# DDR4_Slot.net
KiCad netlist of a schematic drawn in Altium Designer
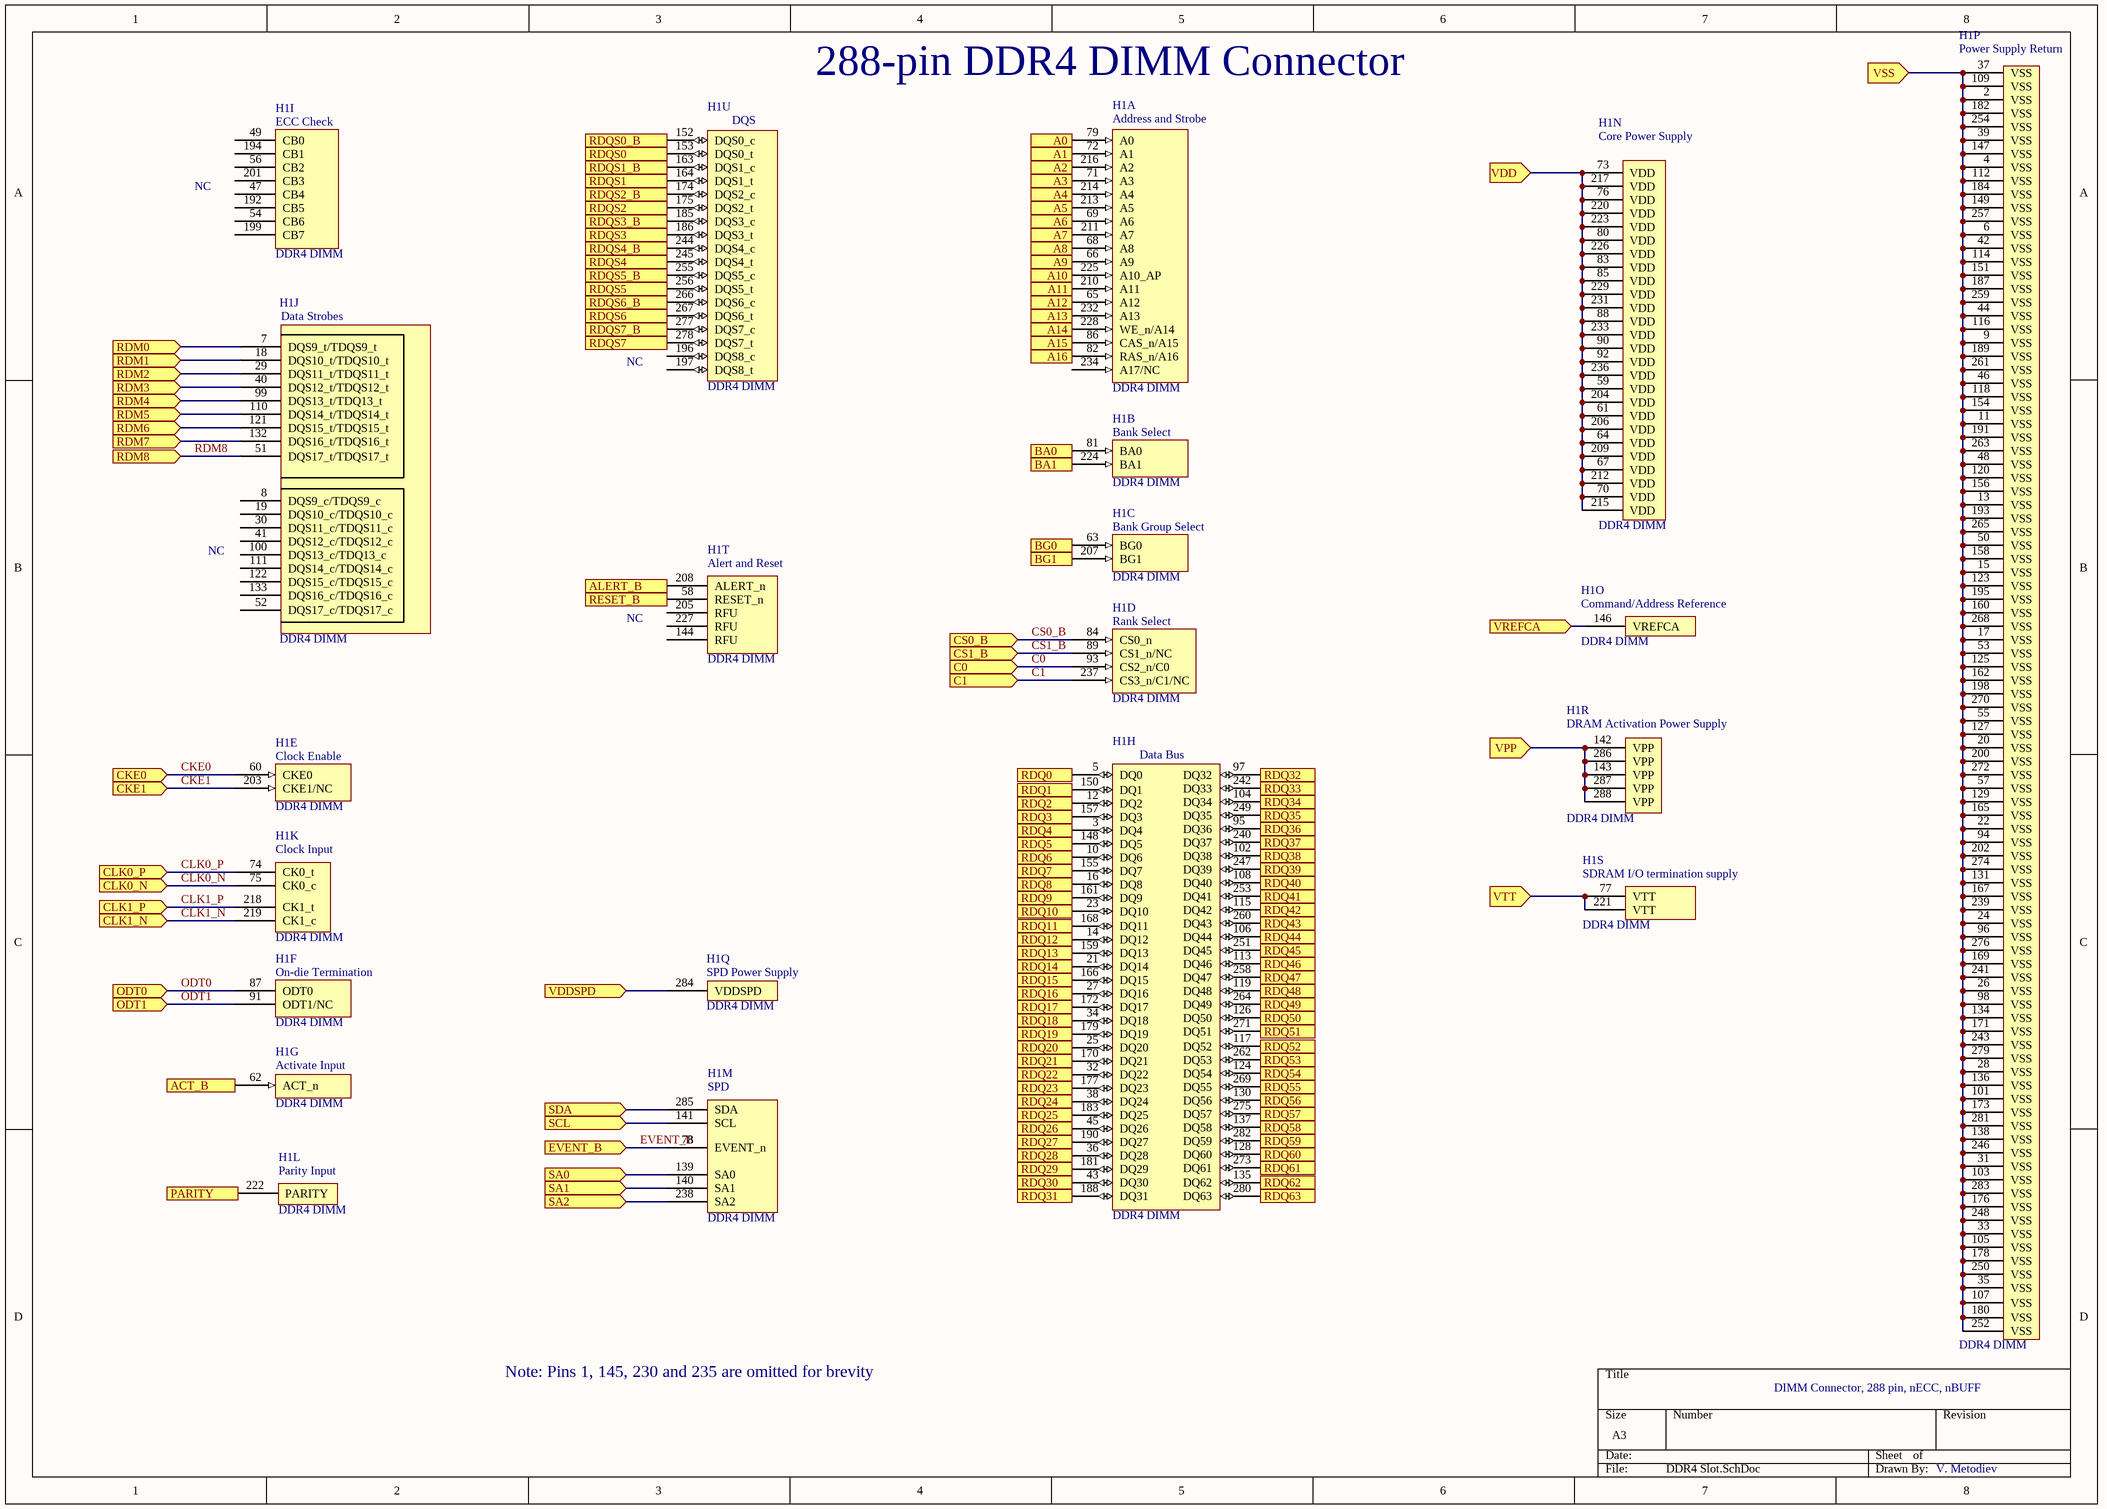
[diagram p0: DDR4 Slot.SchDoc]

(export (version "E")
  (design (tool "Eeschema 10.0.6"))
  (components
    (comp (ref "H1")
      (value "DDR4 DIMM")
      (footprint "DDR4 DIMM")
      (libsource (lib "RouterSchLib") (part "DDR4 DIMM"))
    )
  )
  (nets
    (net (code "1") (name "/A0") (class "Default")
      (node (ref "H1") (pin "79") (pinfunction "A0_79") (pintype "input"))
    )
    (net (code "2") (name "/A1") (class "Default")
      (node (ref "H1") (pin "72") (pinfunction "A1_72") (pintype "input"))
    )
    (net (code "3") (name "/A2") (class "Default")
      (node (ref "H1") (pin "216") (pinfunction "A2_216") (pintype "input"))
    )
    (net (code "4") (name "/A3") (class "Default")
      (node (ref "H1") (pin "71") (pinfunction "A3_71") (pintype "input"))
    )
    (net (code "5") (name "/A4") (class "Default")
      (node (ref "H1") (pin "214") (pinfunction "A4_214") (pintype "input"))
    )
    (net (code "6") (name "/A5") (class "Default")
      (node (ref "H1") (pin "213") (pinfunction "A5_213") (pintype "input"))
    )
    (net (code "7") (name "/A6") (class "Default")
      (node (ref "H1") (pin "69") (pinfunction "A6_69") (pintype "input"))
    )
    (net (code "8") (name "/A7") (class "Default")
      (node (ref "H1") (pin "211") (pinfunction "A7_211") (pintype "input"))
    )
    (net (code "9") (name "/A8") (class "Default")
      (node (ref "H1") (pin "68") (pinfunction "A8_68") (pintype "input"))
    )
    (net (code "10") (name "/A9") (class "Default")
      (node (ref "H1") (pin "66") (pinfunction "A9_66") (pintype "input"))
    )
    (net (code "11") (name "/A10") (class "Default")
      (node (ref "H1") (pin "225") (pinfunction "A10_AP_225") (pintype "input"))
    )
    (net (code "12") (name "/A11") (class "Default")
      (node (ref "H1") (pin "210") (pinfunction "A11_210") (pintype "input"))
    )
    (net (code "13") (name "/A12") (class "Default")
      (node (ref "H1") (pin "65") (pinfunction "A12_65") (pintype "input"))
    )
    (net (code "14") (name "/A13") (class "Default")
      (node (ref "H1") (pin "232") (pinfunction "A13_232") (pintype "input"))
    )
    (net (code "15") (name "/A14") (class "Default")
      (node (ref "H1") (pin "228") (pinfunction "WE_n/A14_228") (pintype "input"))
    )
    (net (code "16") (name "/A15") (class "Default")
      (node (ref "H1") (pin "86") (pinfunction "CAS_n/A15_86") (pintype "input"))
    )
    (net (code "17") (name "/A16") (class "Default")
      (node (ref "H1") (pin "82") (pinfunction "RAS_n/A16_82") (pintype "input"))
    )
    (net (code "18") (name "/ACT_B") (class "Default")
      (node (ref "H1") (pin "62") (pinfunction "ACT_n_62") (pintype "input"))
    )
    (net (code "19") (name "/ALERT_B") (class "Default")
      (node (ref "H1") (pin "208") (pinfunction "ALERT_n_208") (pintype "passive"))
    )
    (net (code "20") (name "/BA0") (class "Default")
      (node (ref "H1") (pin "81") (pinfunction "BA0_81") (pintype "input"))
    )
    (net (code "21") (name "/BA1") (class "Default")
      (node (ref "H1") (pin "224") (pinfunction "BA1_224") (pintype "input"))
    )
    (net (code "22") (name "/BG0") (class "Default")
      (node (ref "H1") (pin "63") (pinfunction "BG0_63") (pintype "input"))
    )
    (net (code "23") (name "/BG1") (class "Default")
      (node (ref "H1") (pin "207") (pinfunction "BG1_207") (pintype "input"))
    )
    (net (code "24") (name "/C0") (class "Default")
      (node (ref "H1") (pin "93") (pinfunction "CS2_n/C0_93") (pintype "input"))
    )
    (net (code "25") (name "/C1") (class "Default")
      (node (ref "H1") (pin "237") (pinfunction "CS3_n/C1/NC_237") (pintype "input"))
    )
    (net (code "26") (name "/CKE0") (class "Default")
      (node (ref "H1") (pin "60") (pinfunction "CKE0_60") (pintype "input"))
    )
    (net (code "27") (name "/CKE1") (class "Default")
      (node (ref "H1") (pin "203") (pinfunction "CKE1/NC_203") (pintype "input"))
    )
    (net (code "28") (name "/CLK0_N") (class "Default")
      (node (ref "H1") (pin "75") (pinfunction "CK0_c_75") (pintype "passive"))
    )
    (net (code "29") (name "/CLK0_P") (class "Default")
      (node (ref "H1") (pin "74") (pinfunction "CK0_t_74") (pintype "passive"))
    )
    (net (code "30") (name "/CLK1_N") (class "Default")
      (node (ref "H1") (pin "219") (pinfunction "CK1_c_219") (pintype "passive"))
    )
    (net (code "31") (name "/CLK1_P") (class "Default")
      (node (ref "H1") (pin "218") (pinfunction "CK1_t_218") (pintype "passive"))
    )
    (net (code "32") (name "/CS0_B") (class "Default")
      (node (ref "H1") (pin "84") (pinfunction "CS0_n_84") (pintype "input"))
    )
    (net (code "33") (name "/CS1_B") (class "Default")
      (node (ref "H1") (pin "89") (pinfunction "CS1_n/NC_89") (pintype "input"))
    )
    (net (code "34") (name "/EVENT_B") (class "Default")
      (node (ref "H1") (pin "78") (pinfunction "EVENT_n_78") (pintype "passive"))
    )
    (net (code "35") (name "/ODT0") (class "Default")
      (node (ref "H1") (pin "87") (pinfunction "ODT0_87") (pintype "passive"))
    )
    (net (code "36") (name "/ODT1") (class "Default")
      (node (ref "H1") (pin "91") (pinfunction "ODT1/NC_91") (pintype "passive"))
    )
    (net (code "37") (name "/PARITY") (class "Default")
      (node (ref "H1") (pin "222") (pinfunction "PARITY_222") (pintype "passive"))
    )
    (net (code "38") (name "/RDM0") (class "Default")
      (node (ref "H1") (pin "7") (pinfunction "DQS9_t/TDQS9_t_7") (pintype "passive"))
    )
    (net (code "39") (name "/RDM1") (class "Default")
      (node (ref "H1") (pin "18") (pinfunction "DQS10_t/TDQS10_t_18") (pintype "passive"))
    )
    (net (code "40") (name "/RDM2") (class "Default")
      (node (ref "H1") (pin "29") (pinfunction "DQS11_t/TDQS11_t_29") (pintype "passive"))
    )
    (net (code "41") (name "/RDM3") (class "Default")
      (node (ref "H1") (pin "40") (pinfunction "DQS12_t/TDQS12_t_40") (pintype "passive"))
    )
    (net (code "42") (name "/RDM4") (class "Default")
      (node (ref "H1") (pin "99") (pinfunction "DQS13_t/TDQ13_t_99") (pintype "passive"))
    )
    (net (code "43") (name "/RDM5") (class "Default")
      (node (ref "H1") (pin "110") (pinfunction "DQS14_t/TDQS14_t_110") (pintype "passive"))
    )
    (net (code "44") (name "/RDM6") (class "Default")
      (node (ref "H1") (pin "121") (pinfunction "DQS15_t/TDQS15_t_121") (pintype "passive"))
    )
    (net (code "45") (name "/RDM7") (class "Default")
      (node (ref "H1") (pin "132") (pinfunction "DQS16_t/TDQS16_t_132") (pintype "passive"))
    )
    (net (code "46") (name "/RDM8") (class "Default")
      (node (ref "H1") (pin "51") (pinfunction "DQS17_t/TDQS17_t_51") (pintype "passive"))
    )
    (net (code "47") (name "/RDQ0") (class "Default")
      (node (ref "H1") (pin "5") (pinfunction "DQ0_5") (pintype "bidirectional"))
    )
    (net (code "48") (name "/RDQ1") (class "Default")
      (node (ref "H1") (pin "150") (pinfunction "DQ1_150") (pintype "bidirectional"))
    )
    (net (code "49") (name "/RDQ2") (class "Default")
      (node (ref "H1") (pin "12") (pinfunction "DQ2_12") (pintype "bidirectional"))
    )
    (net (code "50") (name "/RDQ3") (class "Default")
      (node (ref "H1") (pin "157") (pinfunction "DQ3_157") (pintype "bidirectional"))
    )
    (net (code "51") (name "/RDQ4") (class "Default")
      (node (ref "H1") (pin "3") (pinfunction "DQ4_3") (pintype "bidirectional"))
    )
    (net (code "52") (name "/RDQ5") (class "Default")
      (node (ref "H1") (pin "148") (pinfunction "DQ5_148") (pintype "bidirectional"))
    )
    (net (code "53") (name "/RDQ6") (class "Default")
      (node (ref "H1") (pin "10") (pinfunction "DQ6_10") (pintype "bidirectional"))
    )
    (net (code "54") (name "/RDQ7") (class "Default")
      (node (ref "H1") (pin "155") (pinfunction "DQ7_155") (pintype "bidirectional"))
    )
    (net (code "55") (name "/RDQ8") (class "Default")
      (node (ref "H1") (pin "16") (pinfunction "DQ8_16") (pintype "bidirectional"))
    )
    (net (code "56") (name "/RDQ9") (class "Default")
      (node (ref "H1") (pin "161") (pinfunction "DQ9_161") (pintype "bidirectional"))
    )
    (net (code "57") (name "/RDQ10") (class "Default")
      (node (ref "H1") (pin "23") (pinfunction "DQ10_23") (pintype "bidirectional"))
    )
    (net (code "58") (name "/RDQ11") (class "Default")
      (node (ref "H1") (pin "168") (pinfunction "DQ11_168") (pintype "bidirectional"))
    )
    (net (code "59") (name "/RDQ12") (class "Default")
      (node (ref "H1") (pin "14") (pinfunction "DQ12_14") (pintype "bidirectional"))
    )
    (net (code "60") (name "/RDQ13") (class "Default")
      (node (ref "H1") (pin "159") (pinfunction "DQ13_159") (pintype "bidirectional"))
    )
    (net (code "61") (name "/RDQ14") (class "Default")
      (node (ref "H1") (pin "21") (pinfunction "DQ14_21") (pintype "bidirectional"))
    )
    (net (code "62") (name "/RDQ15") (class "Default")
      (node (ref "H1") (pin "166") (pinfunction "DQ15_166") (pintype "bidirectional"))
    )
    (net (code "63") (name "/RDQ16") (class "Default")
      (node (ref "H1") (pin "27") (pinfunction "DQ16_27") (pintype "bidirectional"))
    )
    (net (code "64") (name "/RDQ17") (class "Default")
      (node (ref "H1") (pin "172") (pinfunction "DQ17_172") (pintype "bidirectional"))
    )
    (net (code "65") (name "/RDQ18") (class "Default")
      (node (ref "H1") (pin "34") (pinfunction "DQ18_34") (pintype "bidirectional"))
    )
    (net (code "66") (name "/RDQ19") (class "Default")
      (node (ref "H1") (pin "179") (pinfunction "DQ19_179") (pintype "bidirectional"))
    )
    (net (code "67") (name "/RDQ20") (class "Default")
      (node (ref "H1") (pin "25") (pinfunction "DQ20_25") (pintype "bidirectional"))
    )
    (net (code "68") (name "/RDQ21") (class "Default")
      (node (ref "H1") (pin "170") (pinfunction "DQ21_170") (pintype "bidirectional"))
    )
    (net (code "69") (name "/RDQ22") (class "Default")
      (node (ref "H1") (pin "32") (pinfunction "DQ22_32") (pintype "bidirectional"))
    )
    (net (code "70") (name "/RDQ23") (class "Default")
      (node (ref "H1") (pin "177") (pinfunction "DQ23_177") (pintype "bidirectional"))
    )
    (net (code "71") (name "/RDQ24") (class "Default")
      (node (ref "H1") (pin "38") (pinfunction "DQ24_38") (pintype "bidirectional"))
    )
    (net (code "72") (name "/RDQ25") (class "Default")
      (node (ref "H1") (pin "183") (pinfunction "DQ25_183") (pintype "bidirectional"))
    )
    (net (code "73") (name "/RDQ26") (class "Default")
      (node (ref "H1") (pin "45") (pinfunction "DQ26_45") (pintype "bidirectional"))
    )
    (net (code "74") (name "/RDQ27") (class "Default")
      (node (ref "H1") (pin "190") (pinfunction "DQ27_190") (pintype "bidirectional"))
    )
    (net (code "75") (name "/RDQ28") (class "Default")
      (node (ref "H1") (pin "36") (pinfunction "DQ28_36") (pintype "bidirectional"))
    )
    (net (code "76") (name "/RDQ29") (class "Default")
      (node (ref "H1") (pin "181") (pinfunction "DQ29_181") (pintype "bidirectional"))
    )
    (net (code "77") (name "/RDQ30") (class "Default")
      (node (ref "H1") (pin "43") (pinfunction "DQ30_43") (pintype "bidirectional"))
    )
    (net (code "78") (name "/RDQ31") (class "Default")
      (node (ref "H1") (pin "188") (pinfunction "DQ31_188") (pintype "bidirectional"))
    )
    (net (code "79") (name "/RDQ32") (class "Default")
      (node (ref "H1") (pin "97") (pinfunction "DQ32_97") (pintype "bidirectional"))
    )
    (net (code "80") (name "/RDQ33") (class "Default")
      (node (ref "H1") (pin "242") (pinfunction "DQ33_242") (pintype "bidirectional"))
    )
    (net (code "81") (name "/RDQ34") (class "Default")
      (node (ref "H1") (pin "104") (pinfunction "DQ34_104") (pintype "bidirectional"))
    )
    (net (code "82") (name "/RDQ35") (class "Default")
      (node (ref "H1") (pin "249") (pinfunction "DQ35_249") (pintype "bidirectional"))
    )
    (net (code "83") (name "/RDQ36") (class "Default")
      (node (ref "H1") (pin "95") (pinfunction "DQ36_95") (pintype "bidirectional"))
    )
    (net (code "84") (name "/RDQ37") (class "Default")
      (node (ref "H1") (pin "240") (pinfunction "DQ37_240") (pintype "bidirectional"))
    )
    (net (code "85") (name "/RDQ38") (class "Default")
      (node (ref "H1") (pin "102") (pinfunction "DQ38_102") (pintype "bidirectional"))
    )
    (net (code "86") (name "/RDQ39") (class "Default")
      (node (ref "H1") (pin "247") (pinfunction "DQ39_247") (pintype "bidirectional"))
    )
    (net (code "87") (name "/RDQ40") (class "Default")
      (node (ref "H1") (pin "108") (pinfunction "DQ40_108") (pintype "bidirectional"))
    )
    (net (code "88") (name "/RDQ41") (class "Default")
      (node (ref "H1") (pin "253") (pinfunction "DQ41_253") (pintype "bidirectional"))
    )
    (net (code "89") (name "/RDQ42") (class "Default")
      (node (ref "H1") (pin "115") (pinfunction "DQ42_115") (pintype "bidirectional"))
    )
    (net (code "90") (name "/RDQ43") (class "Default")
      (node (ref "H1") (pin "260") (pinfunction "DQ43_260") (pintype "bidirectional"))
    )
    (net (code "91") (name "/RDQ44") (class "Default")
      (node (ref "H1") (pin "106") (pinfunction "DQ44_106") (pintype "bidirectional"))
    )
    (net (code "92") (name "/RDQ45") (class "Default")
      (node (ref "H1") (pin "251") (pinfunction "DQ45_251") (pintype "bidirectional"))
    )
    (net (code "93") (name "/RDQ46") (class "Default")
      (node (ref "H1") (pin "113") (pinfunction "DQ46_113") (pintype "bidirectional"))
    )
    (net (code "94") (name "/RDQ47") (class "Default")
      (node (ref "H1") (pin "258") (pinfunction "DQ47_258") (pintype "bidirectional"))
    )
    (net (code "95") (name "/RDQ48") (class "Default")
      (node (ref "H1") (pin "119") (pinfunction "DQ48_119") (pintype "bidirectional"))
    )
    (net (code "96") (name "/RDQ49") (class "Default")
      (node (ref "H1") (pin "264") (pinfunction "DQ49_264") (pintype "bidirectional"))
    )
    (net (code "97") (name "/RDQ50") (class "Default")
      (node (ref "H1") (pin "126") (pinfunction "DQ50_126") (pintype "bidirectional"))
    )
    (net (code "98") (name "/RDQ51") (class "Default")
      (node (ref "H1") (pin "271") (pinfunction "DQ51_271") (pintype "bidirectional"))
    )
    (net (code "99") (name "/RDQ52") (class "Default")
      (node (ref "H1") (pin "117") (pinfunction "DQ52_117") (pintype "bidirectional"))
    )
    (net (code "100") (name "/RDQ53") (class "Default")
      (node (ref "H1") (pin "262") (pinfunction "DQ53_262") (pintype "bidirectional"))
    )
    (net (code "101") (name "/RDQ54") (class "Default")
      (node (ref "H1") (pin "124") (pinfunction "DQ54_124") (pintype "bidirectional"))
    )
    (net (code "102") (name "/RDQ55") (class "Default")
      (node (ref "H1") (pin "269") (pinfunction "DQ55_269") (pintype "bidirectional"))
    )
    (net (code "103") (name "/RDQ56") (class "Default")
      (node (ref "H1") (pin "130") (pinfunction "DQ56_130") (pintype "bidirectional"))
    )
    (net (code "104") (name "/RDQ57") (class "Default")
      (node (ref "H1") (pin "275") (pinfunction "DQ57_275") (pintype "bidirectional"))
    )
    (net (code "105") (name "/RDQ58") (class "Default")
      (node (ref "H1") (pin "137") (pinfunction "DQ58_137") (pintype "bidirectional"))
    )
    (net (code "106") (name "/RDQ59") (class "Default")
      (node (ref "H1") (pin "282") (pinfunction "DQ59_282") (pintype "bidirectional"))
    )
    (net (code "107") (name "/RDQ60") (class "Default")
      (node (ref "H1") (pin "128") (pinfunction "DQ60_128") (pintype "bidirectional"))
    )
    (net (code "108") (name "/RDQ61") (class "Default")
      (node (ref "H1") (pin "273") (pinfunction "DQ61_273") (pintype "bidirectional"))
    )
    (net (code "109") (name "/RDQ62") (class "Default")
      (node (ref "H1") (pin "135") (pinfunction "DQ62_135") (pintype "bidirectional"))
    )
    (net (code "110") (name "/RDQ63") (class "Default")
      (node (ref "H1") (pin "280") (pinfunction "DQ63_280") (pintype "bidirectional"))
    )
    (net (code "111") (name "/RDQS0") (class "Default")
      (node (ref "H1") (pin "153") (pinfunction "DQS0_t_153") (pintype "bidirectional"))
    )
    (net (code "112") (name "/RDQS0_B") (class "Default")
      (node (ref "H1") (pin "152") (pinfunction "DQS0_c_152") (pintype "bidirectional"))
    )
    (net (code "113") (name "/RDQS1") (class "Default")
      (node (ref "H1") (pin "164") (pinfunction "DQS1_t_164") (pintype "bidirectional"))
    )
    (net (code "114") (name "/RDQS1_B") (class "Default")
      (node (ref "H1") (pin "163") (pinfunction "DQS1_c_163") (pintype "bidirectional"))
    )
    (net (code "115") (name "/RDQS2") (class "Default")
      (node (ref "H1") (pin "175") (pinfunction "DQS2_t_175") (pintype "bidirectional"))
    )
    (net (code "116") (name "/RDQS2_B") (class "Default")
      (node (ref "H1") (pin "174") (pinfunction "DQS2_c_174") (pintype "bidirectional"))
    )
    (net (code "117") (name "/RDQS3") (class "Default")
      (node (ref "H1") (pin "186") (pinfunction "DQS3_t_186") (pintype "bidirectional"))
    )
    (net (code "118") (name "/RDQS3_B") (class "Default")
      (node (ref "H1") (pin "185") (pinfunction "DQS3_c_185") (pintype "bidirectional"))
    )
    (net (code "119") (name "/RDQS4") (class "Default")
      (node (ref "H1") (pin "245") (pinfunction "DQS4_t_245") (pintype "bidirectional"))
    )
    (net (code "120") (name "/RDQS4_B") (class "Default")
      (node (ref "H1") (pin "244") (pinfunction "DQS4_c_244") (pintype "bidirectional"))
    )
    (net (code "121") (name "/RDQS5") (class "Default")
      (node (ref "H1") (pin "256") (pinfunction "DQS5_t_256") (pintype "bidirectional"))
    )
    (net (code "122") (name "/RDQS5_B") (class "Default")
      (node (ref "H1") (pin "255") (pinfunction "DQS5_c_255") (pintype "bidirectional"))
    )
    (net (code "123") (name "/RDQS6") (class "Default")
      (node (ref "H1") (pin "267") (pinfunction "DQS6_t_267") (pintype "bidirectional"))
    )
    (net (code "124") (name "/RDQS6_B") (class "Default")
      (node (ref "H1") (pin "266") (pinfunction "DQS6_c_266") (pintype "bidirectional"))
    )
    (net (code "125") (name "/RDQS7") (class "Default")
      (node (ref "H1") (pin "278") (pinfunction "DQS7_t_278") (pintype "bidirectional"))
    )
    (net (code "126") (name "/RDQS7_B") (class "Default")
      (node (ref "H1") (pin "277") (pinfunction "DQS7_c_277") (pintype "bidirectional"))
    )
    (net (code "127") (name "/RESET_B") (class "Default")
      (node (ref "H1") (pin "58") (pinfunction "RESET_n_58") (pintype "passive"))
    )
    (net (code "128") (name "/SA0") (class "Default")
      (node (ref "H1") (pin "139") (pinfunction "SA0_139") (pintype "passive"))
    )
    (net (code "129") (name "/SA1") (class "Default")
      (node (ref "H1") (pin "140") (pinfunction "SA1_140") (pintype "passive"))
    )
    (net (code "130") (name "/SA2") (class "Default")
      (node (ref "H1") (pin "238") (pinfunction "SA2_238") (pintype "passive"))
    )
    (net (code "131") (name "/SCL") (class "Default")
      (node (ref "H1") (pin "141") (pinfunction "SCL_141") (pintype "passive"))
    )
    (net (code "132") (name "/SDA") (class "Default")
      (node (ref "H1") (pin "285") (pinfunction "SDA_285") (pintype "passive"))
    )
    (net (code "133") (name "/VDD") (class "Default")
      (node (ref "H1") (pin "204") (pinfunction "VDD_204") (pintype "passive"))
      (node (ref "H1") (pin "206") (pinfunction "VDD_206") (pintype "passive"))
      (node (ref "H1") (pin "209") (pinfunction "VDD_209") (pintype "passive"))
      (node (ref "H1") (pin "212") (pinfunction "VDD_212") (pintype "passive"))
      (node (ref "H1") (pin "215") (pinfunction "VDD_215") (pintype "passive"))
      (node (ref "H1") (pin "217") (pinfunction "VDD_217") (pintype "passive"))
      (node (ref "H1") (pin "220") (pinfunction "VDD_220") (pintype "passive"))
      (node (ref "H1") (pin "223") (pinfunction "VDD_223") (pintype "passive"))
      (node (ref "H1") (pin "226") (pinfunction "VDD_226") (pintype "passive"))
      (node (ref "H1") (pin "229") (pinfunction "VDD_229") (pintype "passive"))
      (node (ref "H1") (pin "231") (pinfunction "VDD_231") (pintype "passive"))
      (node (ref "H1") (pin "233") (pinfunction "VDD_233") (pintype "passive"))
      (node (ref "H1") (pin "236") (pinfunction "VDD_236") (pintype "passive"))
      (node (ref "H1") (pin "59") (pinfunction "VDD_59") (pintype "passive"))
      (node (ref "H1") (pin "61") (pinfunction "VDD_61") (pintype "passive"))
      (node (ref "H1") (pin "64") (pinfunction "VDD_64") (pintype "passive"))
      (node (ref "H1") (pin "67") (pinfunction "VDD_67") (pintype "passive"))
      (node (ref "H1") (pin "70") (pinfunction "VDD_70") (pintype "passive"))
      (node (ref "H1") (pin "73") (pinfunction "VDD_73") (pintype "passive"))
      (node (ref "H1") (pin "76") (pinfunction "VDD_76") (pintype "passive"))
      (node (ref "H1") (pin "80") (pinfunction "VDD_80") (pintype "passive"))
      (node (ref "H1") (pin "83") (pinfunction "VDD_83") (pintype "passive"))
      (node (ref "H1") (pin "85") (pinfunction "VDD_85") (pintype "passive"))
      (node (ref "H1") (pin "88") (pinfunction "VDD_88") (pintype "passive"))
      (node (ref "H1") (pin "90") (pinfunction "VDD_90") (pintype "passive"))
      (node (ref "H1") (pin "92") (pinfunction "VDD_92") (pintype "passive"))
    )
    (net (code "134") (name "/VDDSPD") (class "Default")
      (node (ref "H1") (pin "284") (pinfunction "VDDSPD_284") (pintype "passive"))
    )
    (net (code "135") (name "/VPP") (class "Default")
      (node (ref "H1") (pin "142") (pinfunction "VPP_142") (pintype "passive"))
      (node (ref "H1") (pin "143") (pinfunction "VPP_143") (pintype "passive"))
      (node (ref "H1") (pin "286") (pinfunction "VPP_286") (pintype "passive"))
      (node (ref "H1") (pin "287") (pinfunction "VPP_287") (pintype "passive"))
      (node (ref "H1") (pin "288") (pinfunction "VPP_288") (pintype "passive"))
    )
    (net (code "136") (name "/VREFCA") (class "Default")
      (node (ref "H1") (pin "146") (pinfunction "VREFCA_146") (pintype "passive"))
    )
    (net (code "137") (name "/VSS") (class "Default")
      (node (ref "H1") (pin "101") (pinfunction "VSS_101") (pintype "passive"))
      (node (ref "H1") (pin "103") (pinfunction "VSS_103") (pintype "passive"))
      (node (ref "H1") (pin "105") (pinfunction "VSS_105") (pintype "passive"))
      (node (ref "H1") (pin "107") (pinfunction "VSS_107") (pintype "passive"))
      (node (ref "H1") (pin "109") (pinfunction "VSS_109") (pintype "passive"))
      (node (ref "H1") (pin "11") (pinfunction "VSS_11") (pintype "passive"))
      (node (ref "H1") (pin "112") (pinfunction "VSS_112") (pintype "passive"))
      (node (ref "H1") (pin "114") (pinfunction "VSS_114") (pintype "passive"))
      (node (ref "H1") (pin "116") (pinfunction "VSS_116") (pintype "passive"))
      (node (ref "H1") (pin "118") (pinfunction "VSS_118") (pintype "passive"))
      (node (ref "H1") (pin "120") (pinfunction "VSS_120") (pintype "passive"))
      (node (ref "H1") (pin "123") (pinfunction "VSS_123") (pintype "passive"))
      (node (ref "H1") (pin "125") (pinfunction "VSS_125") (pintype "passive"))
      (node (ref "H1") (pin "127") (pinfunction "VSS_127") (pintype "passive"))
      (node (ref "H1") (pin "129") (pinfunction "VSS_129") (pintype "passive"))
      (node (ref "H1") (pin "13") (pinfunction "VSS_13") (pintype "passive"))
      (node (ref "H1") (pin "131") (pinfunction "VSS_131") (pintype "passive"))
      (node (ref "H1") (pin "134") (pinfunction "VSS_134") (pintype "passive"))
      (node (ref "H1") (pin "136") (pinfunction "VSS_136") (pintype "passive"))
      (node (ref "H1") (pin "138") (pinfunction "VSS_138") (pintype "passive"))
      (node (ref "H1") (pin "147") (pinfunction "VSS_147") (pintype "passive"))
      (node (ref "H1") (pin "149") (pinfunction "VSS_149") (pintype "passive"))
      (node (ref "H1") (pin "15") (pinfunction "VSS_15") (pintype "passive"))
      (node (ref "H1") (pin "151") (pinfunction "VSS_151") (pintype "passive"))
      (node (ref "H1") (pin "154") (pinfunction "VSS_154") (pintype "passive"))
      (node (ref "H1") (pin "156") (pinfunction "VSS_156") (pintype "passive"))
      (node (ref "H1") (pin "158") (pinfunction "VSS_158") (pintype "passive"))
      (node (ref "H1") (pin "160") (pinfunction "VSS_160") (pintype "passive"))
      (node (ref "H1") (pin "162") (pinfunction "VSS_162") (pintype "passive"))
      (node (ref "H1") (pin "165") (pinfunction "VSS_165") (pintype "passive"))
      (node (ref "H1") (pin "167") (pinfunction "VSS_167") (pintype "passive"))
      (node (ref "H1") (pin "169") (pinfunction "VSS_169") (pintype "passive"))
      (node (ref "H1") (pin "17") (pinfunction "VSS_17") (pintype "passive"))
      (node (ref "H1") (pin "171") (pinfunction "VSS_171") (pintype "passive"))
      (node (ref "H1") (pin "173") (pinfunction "VSS_173") (pintype "passive"))
      (node (ref "H1") (pin "176") (pinfunction "VSS_176") (pintype "passive"))
      (node (ref "H1") (pin "178") (pinfunction "VSS_178") (pintype "passive"))
      (node (ref "H1") (pin "180") (pinfunction "VSS_180") (pintype "passive"))
      (node (ref "H1") (pin "182") (pinfunction "VSS_182") (pintype "passive"))
      (node (ref "H1") (pin "184") (pinfunction "VSS_184") (pintype "passive"))
      (node (ref "H1") (pin "187") (pinfunction "VSS_187") (pintype "passive"))
      (node (ref "H1") (pin "189") (pinfunction "VSS_189") (pintype "passive"))
      (node (ref "H1") (pin "191") (pinfunction "VSS_191") (pintype "passive"))
      (node (ref "H1") (pin "193") (pinfunction "VSS_193") (pintype "passive"))
      (node (ref "H1") (pin "195") (pinfunction "VSS_195") (pintype "passive"))
      (node (ref "H1") (pin "198") (pinfunction "VSS_198") (pintype "passive"))
      (node (ref "H1") (pin "2") (pinfunction "VSS_2") (pintype "passive"))
      (node (ref "H1") (pin "20") (pinfunction "VSS_20") (pintype "passive"))
      (node (ref "H1") (pin "200") (pinfunction "VSS_200") (pintype "passive"))
      (node (ref "H1") (pin "202") (pinfunction "VSS_202") (pintype "passive"))
      (node (ref "H1") (pin "22") (pinfunction "VSS_22") (pintype "passive"))
      (node (ref "H1") (pin "239") (pinfunction "VSS_239") (pintype "passive"))
      (node (ref "H1") (pin "24") (pinfunction "VSS_24") (pintype "passive"))
      (node (ref "H1") (pin "241") (pinfunction "VSS_241") (pintype "passive"))
      (node (ref "H1") (pin "243") (pinfunction "VSS_243") (pintype "passive"))
      (node (ref "H1") (pin "246") (pinfunction "VSS_246") (pintype "passive"))
      (node (ref "H1") (pin "248") (pinfunction "VSS_248") (pintype "passive"))
      (node (ref "H1") (pin "250") (pinfunction "VSS_250") (pintype "passive"))
      (node (ref "H1") (pin "252") (pinfunction "VSS_252") (pintype "passive"))
      (node (ref "H1") (pin "254") (pinfunction "VSS_254") (pintype "passive"))
      (node (ref "H1") (pin "257") (pinfunction "VSS_257") (pintype "passive"))
      (node (ref "H1") (pin "259") (pinfunction "VSS_259") (pintype "passive"))
      (node (ref "H1") (pin "26") (pinfunction "VSS_26") (pintype "passive"))
      (node (ref "H1") (pin "261") (pinfunction "VSS_261") (pintype "passive"))
      (node (ref "H1") (pin "263") (pinfunction "VSS_263") (pintype "passive"))
      (node (ref "H1") (pin "265") (pinfunction "VSS_265") (pintype "passive"))
      (node (ref "H1") (pin "268") (pinfunction "VSS_268") (pintype "passive"))
      (node (ref "H1") (pin "270") (pinfunction "VSS_270") (pintype "passive"))
      (node (ref "H1") (pin "272") (pinfunction "VSS_272") (pintype "passive"))
      (node (ref "H1") (pin "274") (pinfunction "VSS_274") (pintype "passive"))
      (node (ref "H1") (pin "276") (pinfunction "VSS_276") (pintype "passive"))
      (node (ref "H1") (pin "279") (pinfunction "VSS_279") (pintype "passive"))
      (node (ref "H1") (pin "28") (pinfunction "VSS_28") (pintype "passive"))
      (node (ref "H1") (pin "281") (pinfunction "VSS_281") (pintype "passive"))
      (node (ref "H1") (pin "283") (pinfunction "VSS_283") (pintype "passive"))
      (node (ref "H1") (pin "31") (pinfunction "VSS_31") (pintype "passive"))
      (node (ref "H1") (pin "33") (pinfunction "VSS_33") (pintype "passive"))
      (node (ref "H1") (pin "35") (pinfunction "VSS_35") (pintype "passive"))
      (node (ref "H1") (pin "37") (pinfunction "VSS_37") (pintype "passive"))
      (node (ref "H1") (pin "39") (pinfunction "VSS_39") (pintype "passive"))
      (node (ref "H1") (pin "4") (pinfunction "VSS_4") (pintype "passive"))
      (node (ref "H1") (pin "42") (pinfunction "VSS_42") (pintype "passive"))
      (node (ref "H1") (pin "44") (pinfunction "VSS_44") (pintype "passive"))
      (node (ref "H1") (pin "46") (pinfunction "VSS_46") (pintype "passive"))
      (node (ref "H1") (pin "48") (pinfunction "VSS_48") (pintype "passive"))
      (node (ref "H1") (pin "50") (pinfunction "VSS_50") (pintype "passive"))
      (node (ref "H1") (pin "53") (pinfunction "VSS_53") (pintype "passive"))
      (node (ref "H1") (pin "55") (pinfunction "VSS_55") (pintype "passive"))
      (node (ref "H1") (pin "57") (pinfunction "VSS_57") (pintype "passive"))
      (node (ref "H1") (pin "6") (pinfunction "VSS_6") (pintype "passive"))
      (node (ref "H1") (pin "9") (pinfunction "VSS_9") (pintype "passive"))
      (node (ref "H1") (pin "94") (pinfunction "VSS_94") (pintype "passive"))
      (node (ref "H1") (pin "96") (pinfunction "VSS_96") (pintype "passive"))
      (node (ref "H1") (pin "98") (pinfunction "VSS_98") (pintype "passive"))
    )
    (net (code "138") (name "/VTT") (class "Default")
      (node (ref "H1") (pin "221") (pinfunction "VTT_221") (pintype "passive"))
      (node (ref "H1") (pin "77") (pinfunction "VTT_77") (pintype "passive"))
    )
    (net (code "139") (name "unconnected-(H1A-A17{slash}NC-Pad234)") (class "Default")
      (node (ref "H1") (pin "234") (pinfunction "A17/NC_234") (pintype "input"))
    )
    (net (code "140") (name "unconnected-(H1I-CB0-Pad49)") (class "Default")
      (node (ref "H1") (pin "49") (pinfunction "CB0_49") (pintype "passive"))
    )
    (net (code "141") (name "unconnected-(H1I-CB1-Pad194)") (class "Default")
      (node (ref "H1") (pin "194") (pinfunction "CB1_194") (pintype "passive"))
    )
    (net (code "142") (name "unconnected-(H1I-CB2-Pad56)") (class "Default")
      (node (ref "H1") (pin "56") (pinfunction "CB2_56") (pintype "passive"))
    )
    (net (code "143") (name "unconnected-(H1I-CB3-Pad201)") (class "Default")
      (node (ref "H1") (pin "201") (pinfunction "CB3_201") (pintype "passive"))
    )
    (net (code "144") (name "unconnected-(H1I-CB4-Pad47)") (class "Default")
      (node (ref "H1") (pin "47") (pinfunction "CB4_47") (pintype "passive"))
    )
    (net (code "145") (name "unconnected-(H1I-CB5-Pad192)") (class "Default")
      (node (ref "H1") (pin "192") (pinfunction "CB5_192") (pintype "passive"))
    )
    (net (code "146") (name "unconnected-(H1I-CB6-Pad54)") (class "Default")
      (node (ref "H1") (pin "54") (pinfunction "CB6_54") (pintype "passive"))
    )
    (net (code "147") (name "unconnected-(H1I-CB7-Pad199)") (class "Default")
      (node (ref "H1") (pin "199") (pinfunction "CB7_199") (pintype "passive"))
    )
    (net (code "148") (name "unconnected-(H1J-DQS9_c{slash}TDQS9_c-Pad8)") (class "Default")
      (node (ref "H1") (pin "8") (pinfunction "DQS9_c/TDQS9_c_8") (pintype "passive"))
    )
    (net (code "149") (name "unconnected-(H1J-DQS10_c{slash}TDQS10_c-Pad19)") (class "Default")
      (node (ref "H1") (pin "19") (pinfunction "DQS10_c/TDQS10_c_19") (pintype "passive"))
    )
    (net (code "150") (name "unconnected-(H1J-DQS11_c{slash}TDQS11_c-Pad30)") (class "Default")
      (node (ref "H1") (pin "30") (pinfunction "DQS11_c/TDQS11_c_30") (pintype "passive"))
    )
    (net (code "151") (name "unconnected-(H1J-DQS12_c{slash}TDQS12_c-Pad41)") (class "Default")
      (node (ref "H1") (pin "41") (pinfunction "DQS12_c/TDQS12_c_41") (pintype "passive"))
    )
    (net (code "152") (name "unconnected-(H1J-DQS13_c{slash}TDQ13_c-Pad100)") (class "Default")
      (node (ref "H1") (pin "100") (pinfunction "DQS13_c/TDQ13_c_100") (pintype "passive"))
    )
    (net (code "153") (name "unconnected-(H1J-DQS14_c{slash}TDQS14_c-Pad111)") (class "Default")
      (node (ref "H1") (pin "111") (pinfunction "DQS14_c/TDQS14_c_111") (pintype "passive"))
    )
    (net (code "154") (name "unconnected-(H1J-DQS15_c{slash}TDQS15_c-Pad122)") (class "Default")
      (node (ref "H1") (pin "122") (pinfunction "DQS15_c/TDQS15_c_122") (pintype "passive"))
    )
    (net (code "155") (name "unconnected-(H1J-DQS16_c{slash}TDQS16_c-Pad133)") (class "Default")
      (node (ref "H1") (pin "133") (pinfunction "DQS16_c/TDQS16_c_133") (pintype "passive"))
    )
    (net (code "156") (name "unconnected-(H1J-DQS17_c{slash}TDQS17_c-Pad52)") (class "Default")
      (node (ref "H1") (pin "52") (pinfunction "DQS17_c/TDQS17_c_52") (pintype "passive"))
    )
    (net (code "157") (name "unconnected-(H1T-RFU-Pad144)") (class "Default")
      (node (ref "H1") (pin "144") (pinfunction "RFU_144") (pintype "passive"))
    )
    (net (code "158") (name "unconnected-(H1T-RFU-Pad205)") (class "Default")
      (node (ref "H1") (pin "205") (pinfunction "RFU_205") (pintype "passive"))
    )
    (net (code "159") (name "unconnected-(H1T-RFU-Pad227)") (class "Default")
      (node (ref "H1") (pin "227") (pinfunction "RFU_227") (pintype "passive"))
    )
    (net (code "160") (name "unconnected-(H1U-DQS8_c-Pad196)") (class "Default")
      (node (ref "H1") (pin "196") (pinfunction "DQS8_c_196") (pintype "bidirectional"))
    )
    (net (code "161") (name "unconnected-(H1U-DQS8_t-Pad197)") (class "Default")
      (node (ref "H1") (pin "197") (pinfunction "DQS8_t_197") (pintype "bidirectional"))
    )
  )
)
